# CANSniftAndShift.net
KiCad netlist of a schematic drawn in EAGLE
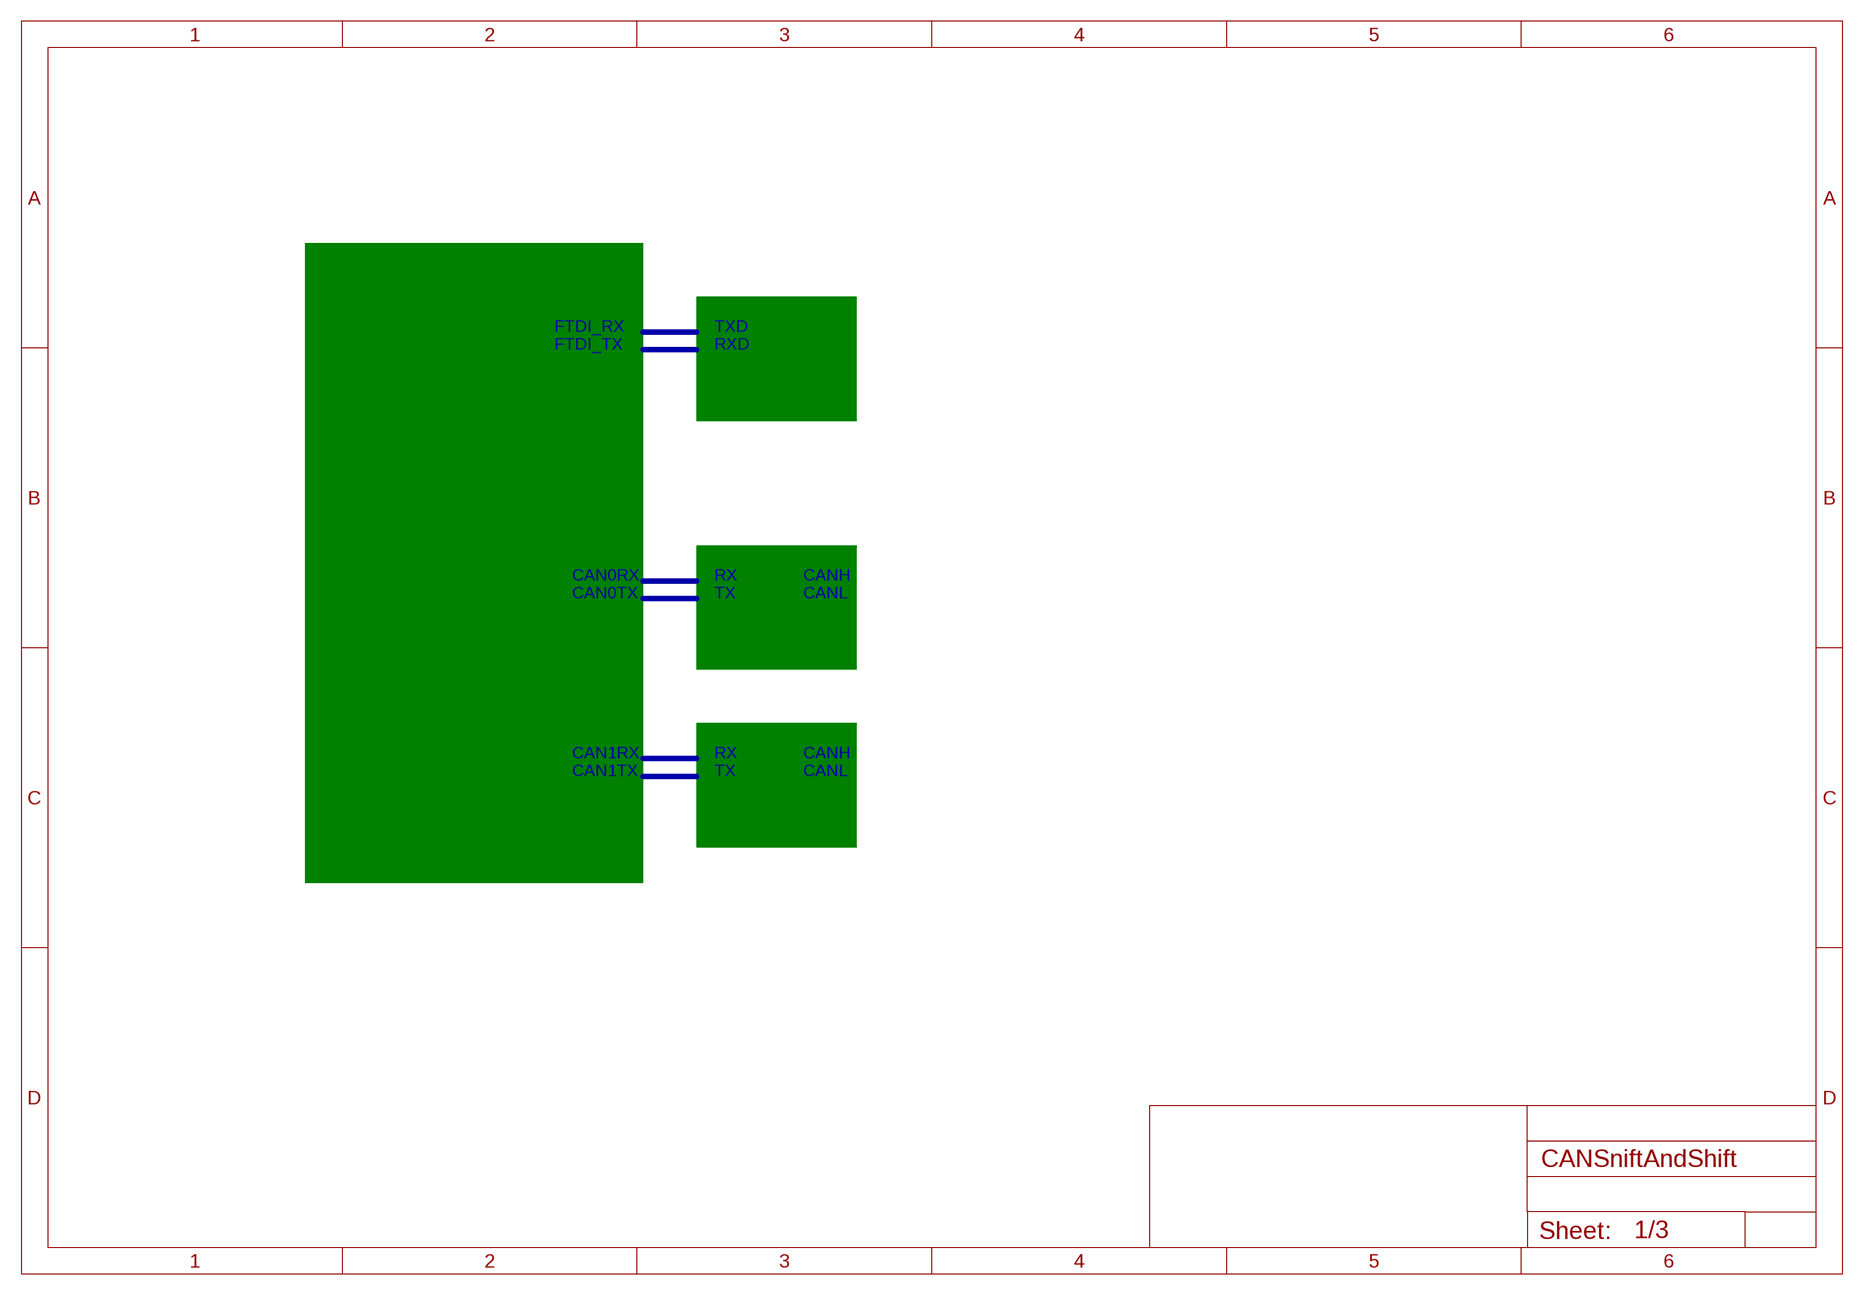
[diagram p0: schematic, sheet 1]
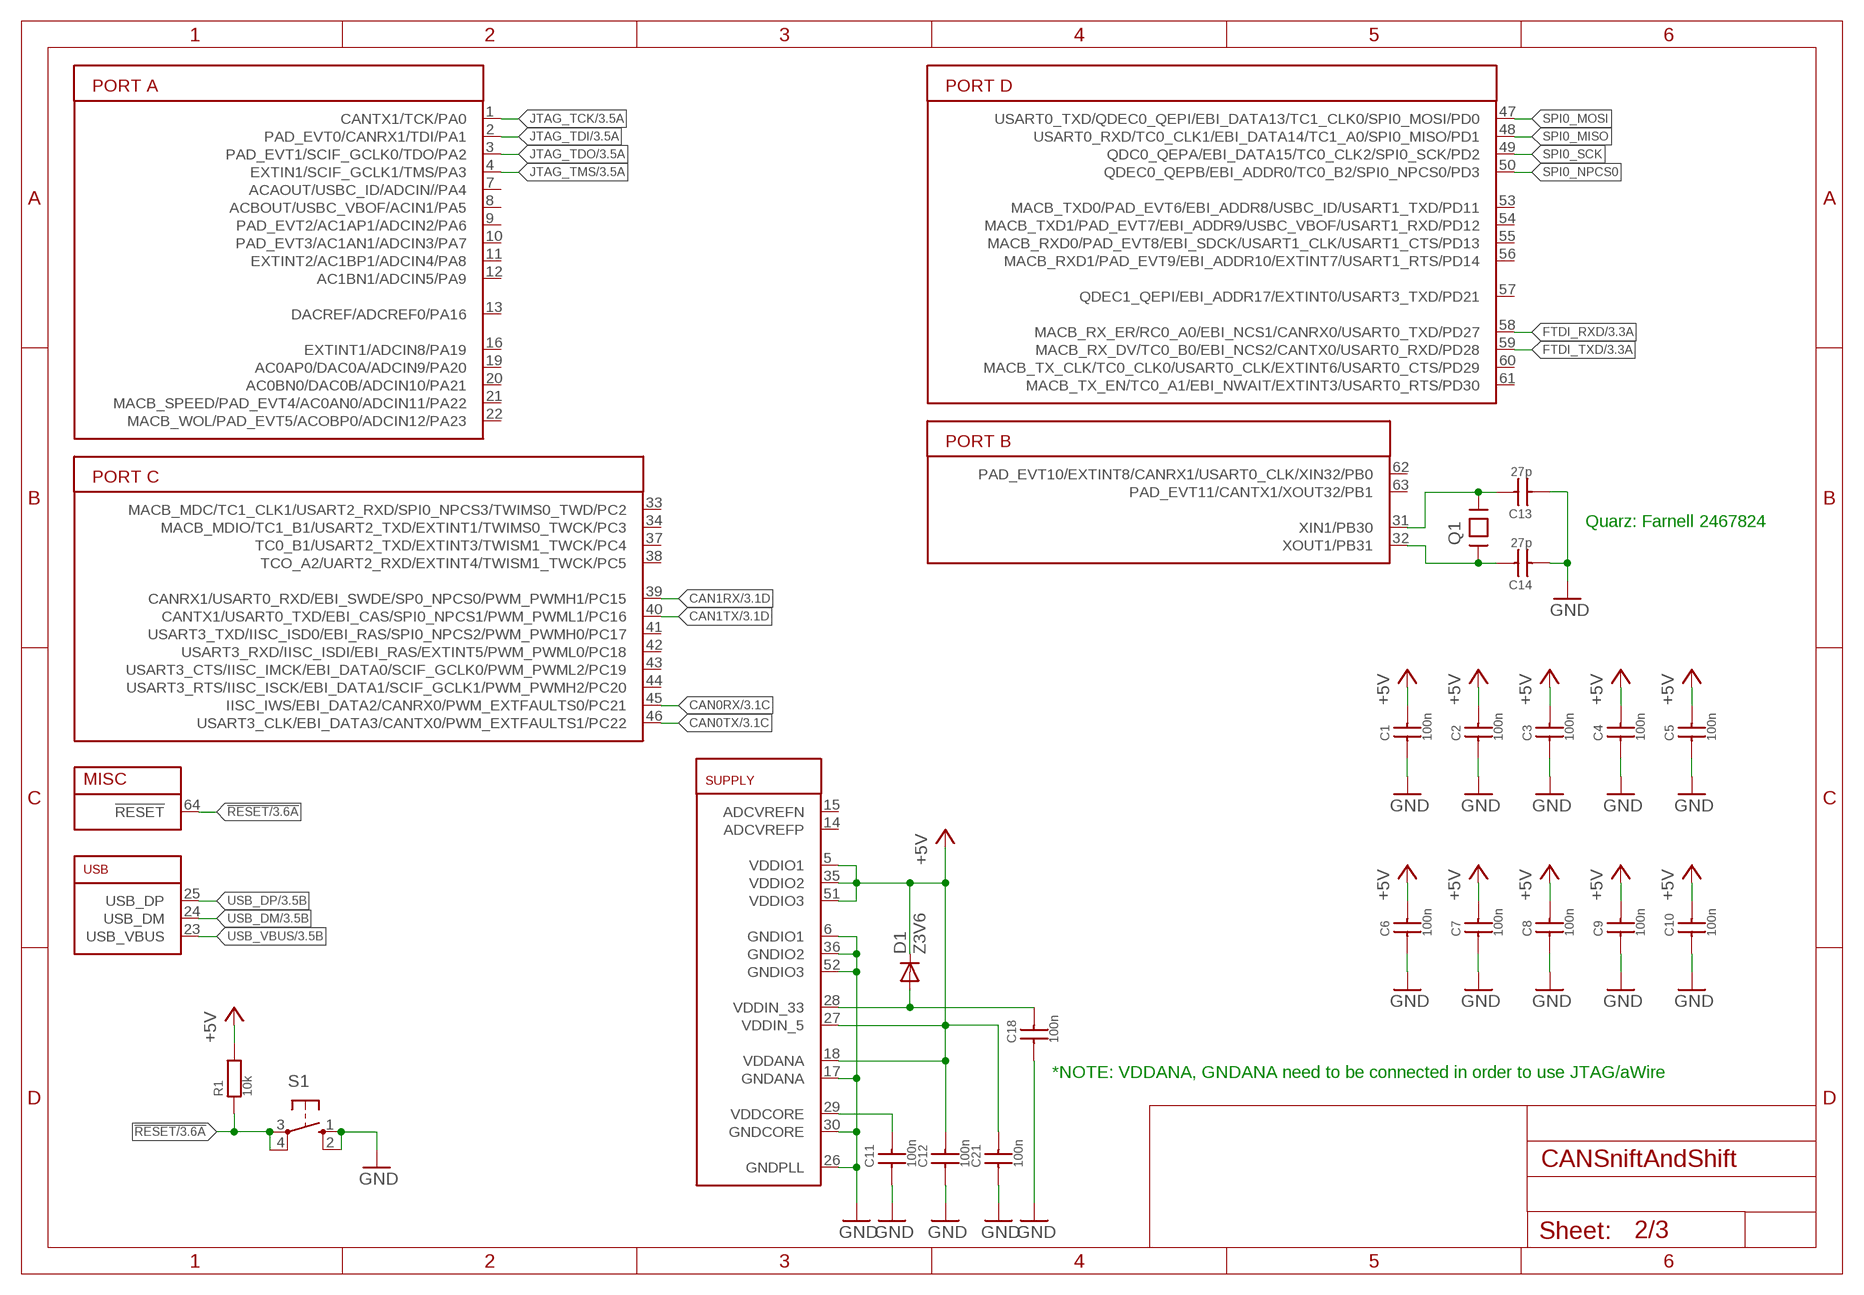
[diagram p1: schematic, sheet 2]
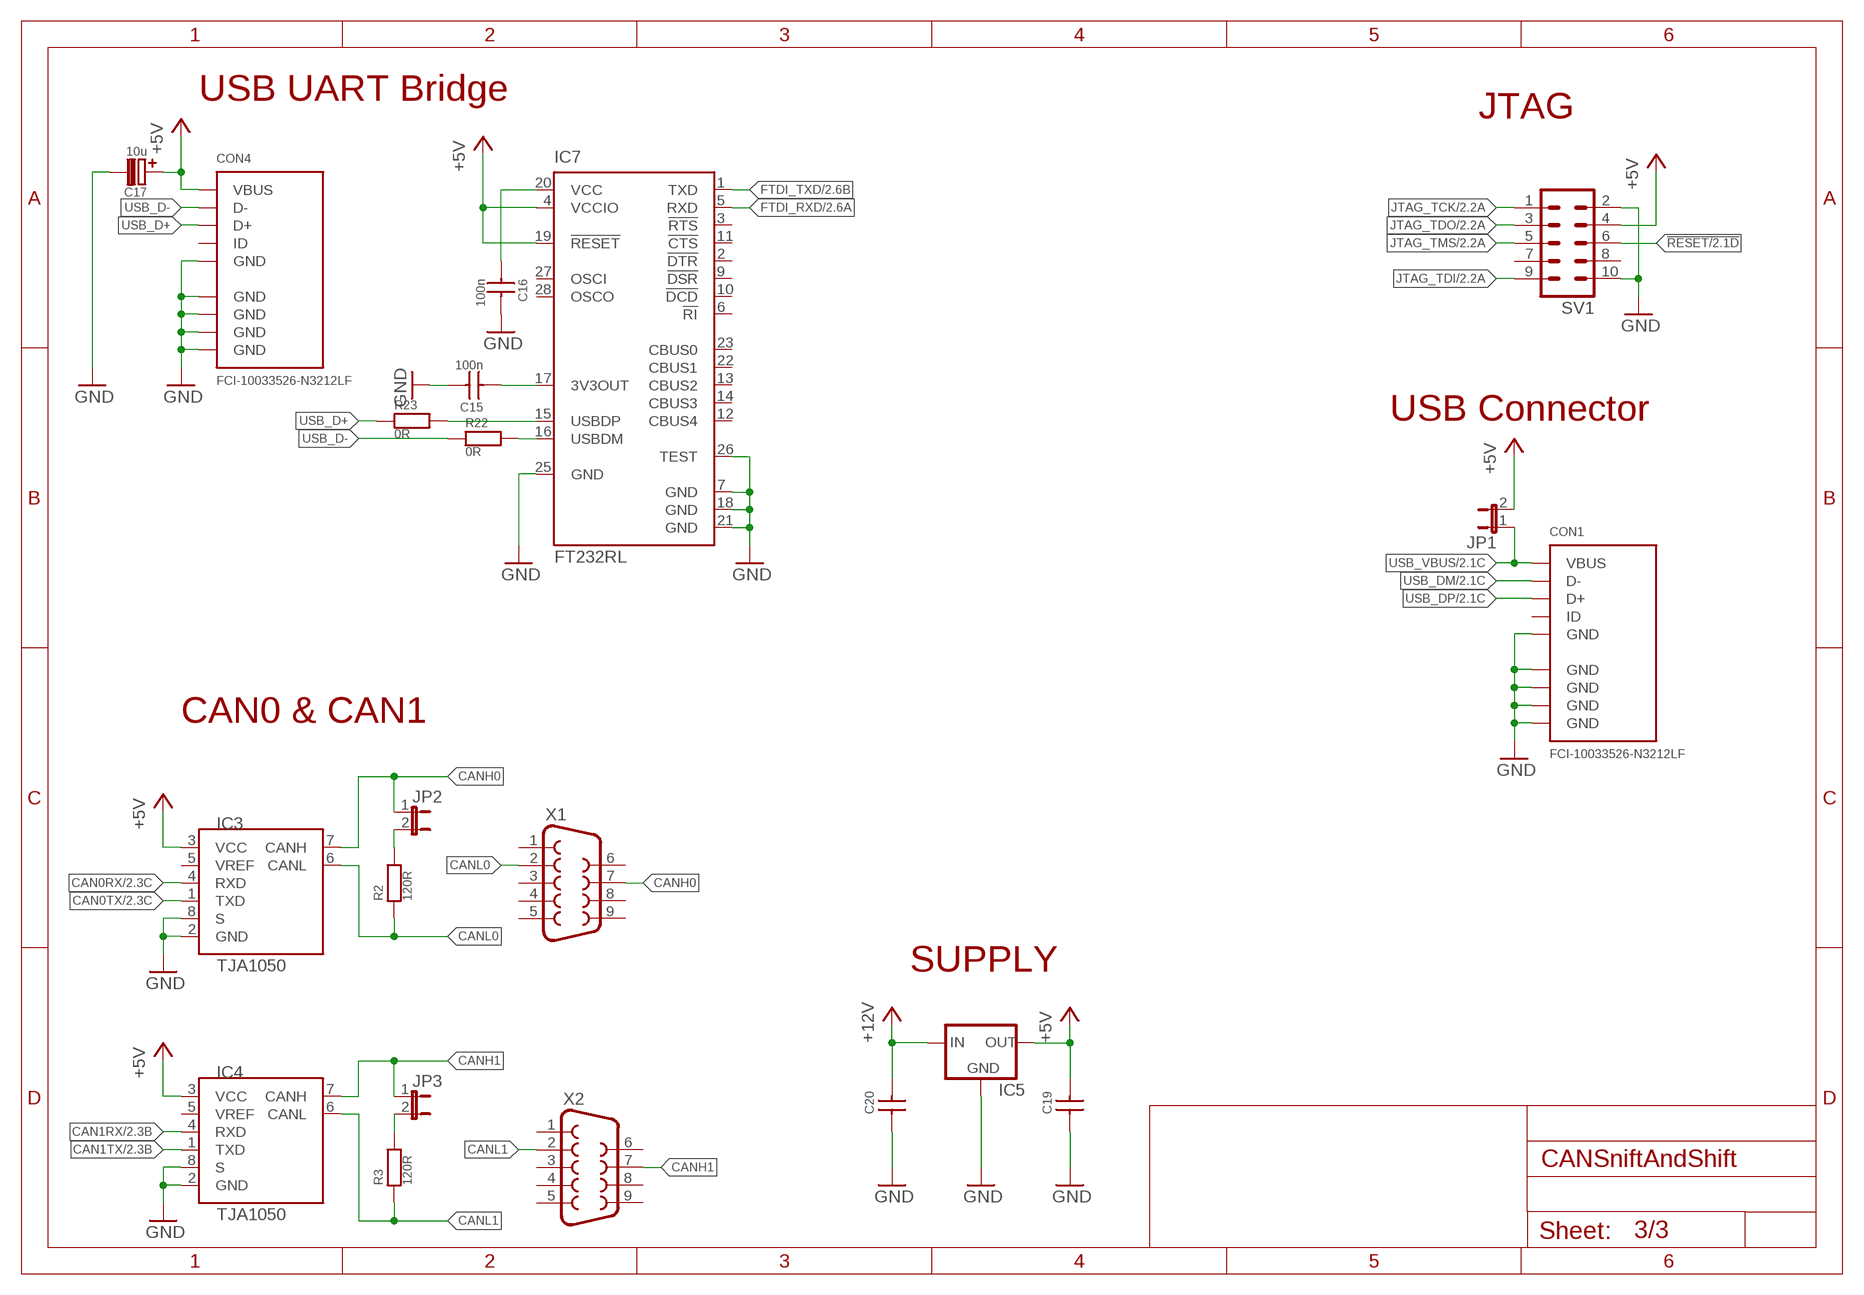
[diagram p2: schematic, sheet 3]

(export (version "E")
  (design (tool "Eeschema 10.0.6"))
  (components
    (comp (ref "C1")
      (value "100n")
      (footprint "eagle-import:C0603")
      (libsource (lib "eagle-import") (part "C_SMD0603"))
    )
    (comp (ref "C2")
      (value "100n")
      (footprint "eagle-import:C0603")
      (libsource (lib "eagle-import") (part "C_SMD0603"))
    )
    (comp (ref "C3")
      (value "100n")
      (footprint "eagle-import:C0603")
      (libsource (lib "eagle-import") (part "C_SMD0603"))
    )
    (comp (ref "C4")
      (value "100n")
      (footprint "eagle-import:C0603")
      (libsource (lib "eagle-import") (part "C_SMD0603"))
    )
    (comp (ref "C5")
      (value "100n")
      (footprint "eagle-import:C0603")
      (libsource (lib "eagle-import") (part "C_SMD0603"))
    )
    (comp (ref "C6")
      (value "100n")
      (footprint "eagle-import:C0603")
      (libsource (lib "eagle-import") (part "C_SMD0603"))
    )
    (comp (ref "C7")
      (value "100n")
      (footprint "eagle-import:C0603")
      (libsource (lib "eagle-import") (part "C_SMD0603"))
    )
    (comp (ref "C8")
      (value "100n")
      (footprint "eagle-import:C0603")
      (libsource (lib "eagle-import") (part "C_SMD0603"))
    )
    (comp (ref "C9")
      (value "100n")
      (footprint "eagle-import:C0603")
      (libsource (lib "eagle-import") (part "C_SMD0603"))
    )
    (comp (ref "C10")
      (value "100n")
      (footprint "eagle-import:C0603")
      (libsource (lib "eagle-import") (part "C_SMD0603"))
    )
    (comp (ref "C11")
      (value "100n")
      (footprint "eagle-import:C0603")
      (libsource (lib "eagle-import") (part "C_SMD0603"))
    )
    (comp (ref "C12")
      (value "100n")
      (footprint "eagle-import:C0603")
      (libsource (lib "eagle-import") (part "C_SMD0603"))
    )
    (comp (ref "C13")
      (value "27p")
      (footprint "eagle-import:C0603")
      (libsource (lib "eagle-import") (part "C_SMD0603"))
    )
    (comp (ref "C14")
      (value "27p")
      (footprint "eagle-import:C0603")
      (libsource (lib "eagle-import") (part "C_SMD0603"))
    )
    (comp (ref "C18")
      (value "100n")
      (footprint "eagle-import:C0603")
      (libsource (lib "eagle-import") (part "C_SMD0603"))
    )
    (comp (ref "C21")
      (value "100n")
      (footprint "eagle-import:C0603")
      (libsource (lib "eagle-import") (part "C_SMD0603"))
    )
    (comp (ref "D1")
      (value "Z3V6")
      (footprint "eagle-import:DO214A")
      (libsource (lib "eagle-import") (part "BZG03C15TR3"))
    )
    (comp (ref "IC1")
      (value "AT32UC3C264C0.5MM")
      (footprint "eagle-import:TQFP64-0.5MM")
      (libsource (lib "eagle-import") (part "AT32UC3C264C0.5MM"))
    )
    (comp (ref "Q1")
      (value "16MHz")
      (footprint "eagle-import:CRYSTAL-ABRACON-ABM7-SMD")
      (libsource (lib "eagle-import") (part "CRYSTAL-ABRACON-ABM7-SMD"))
    )
    (comp (ref "R1")
      (value "10k")
      (footprint "eagle-import:R0603")
      (libsource (lib "eagle-import") (part "R0603"))
    )
    (comp (ref "S1")
      (value "10-XX")
      (footprint "eagle-import:B3F-10XX")
      (fields (field (name "MPN") "B3F-1000"))
      (libsource (lib "eagle-import") (part "10-XX"))
    )
    (comp (ref "C15")
      (value "100n")
      (footprint "eagle-import:C0402")
      (libsource (lib "eagle-import") (part "C_SMD0402"))
    )
    (comp (ref "C16")
      (value "100n")
      (footprint "eagle-import:C0402")
      (libsource (lib "eagle-import") (part "C_SMD0402"))
    )
    (comp (ref "C17")
      (value "10u")
      (footprint "eagle-import:C_POL_4X4MM")
      (libsource (lib "eagle-import") (part "C_POL4X4MM"))
    )
    (comp (ref "C19")
      (value "C_SMD0603")
      (footprint "eagle-import:C0603")
      (libsource (lib "eagle-import") (part "C_SMD0603"))
    )
    (comp (ref "C20")
      (value "C_SMD0603")
      (footprint "eagle-import:C0603")
      (libsource (lib "eagle-import") (part "C_SMD0603"))
    )
    (comp (ref "CON1")
      (value "FCI-10033526-N3212LF")
      (footprint "eagle-import:FCI-10033526-N3212LF")
      (libsource (lib "eagle-import") (part "FCI-10033526-N3212LF"))
    )
    (comp (ref "CON4")
      (value "FCI-10033526-N3212LF")
      (footprint "eagle-import:FCI-10033526-N3212LF")
      (libsource (lib "eagle-import") (part "FCI-10033526-N3212LF"))
    )
    (comp (ref "IC3")
      (value "TJA1050")
      (footprint "eagle-import:SO8")
      (libsource (lib "eagle-import") (part "TJA1050"))
    )
    (comp (ref "IC4")
      (value "TJA1050")
      (footprint "eagle-import:SO8")
      (libsource (lib "eagle-import") (part "TJA1050"))
    )
    (comp (ref "IC5")
      (value "78XXL")
      (footprint "eagle-import:78XXL")
      (libsource (lib "eagle-import") (part "78XXL"))
    )
    (comp (ref "IC7")
      (value "FT232RL")
      (footprint "eagle-import:SSOP28")
      (libsource (lib "eagle-import") (part "FT232RL"))
    )
    (comp (ref "JP1")
      (value "JUMPER2")
      (footprint "eagle-import:JUMPER2_THROUGHHOLE")
      (libsource (lib "eagle-import") (part "JUMPER2"))
    )
    (comp (ref "JP2")
      (value "JUMPER2")
      (footprint "eagle-import:JUMPER2_THROUGHHOLE")
      (libsource (lib "eagle-import") (part "JUMPER2"))
    )
    (comp (ref "JP3")
      (value "JUMPER2")
      (footprint "eagle-import:JUMPER2_THROUGHHOLE")
      (libsource (lib "eagle-import") (part "JUMPER2"))
    )
    (comp (ref "R2")
      (value "120R")
      (footprint "eagle-import:R0603")
      (libsource (lib "eagle-import") (part "R0603"))
    )
    (comp (ref "R3")
      (value "120R")
      (footprint "eagle-import:R0603")
      (libsource (lib "eagle-import") (part "R0603"))
    )
    (comp (ref "R22")
      (value "0R")
      (footprint "eagle-import:R0402")
      (libsource (lib "eagle-import") (part "R0402"))
    )
    (comp (ref "R23")
      (value "0R")
      (footprint "eagle-import:R0402")
      (libsource (lib "eagle-import") (part "R0402"))
    )
    (comp (ref "SV1")
      (value "ML10")
      (footprint "eagle-import:ML10")
      (libsource (lib "eagle-import") (part "ML10"))
    )
    (comp (ref "X1")
      (value "F09HP")
      (footprint "eagle-import:F09HP")
      (libsource (lib "eagle-import") (part "F09HP"))
    )
    (comp (ref "X2")
      (value "F09HP")
      (footprint "eagle-import:F09HP")
      (libsource (lib "eagle-import") (part "F09HP"))
    )
  )
  (nets
    (net (code "1") (name "+5V") (class "Default")
      (node (ref "C1") (pin "2") (pinfunction "P$2_2") (pintype "passive"))
      (node (ref "C10") (pin "2") (pinfunction "P$2_2") (pintype "passive"))
      (node (ref "C12") (pin "2") (pinfunction "P$2_2") (pintype "passive"))
      (node (ref "C17") (pin "+") (pinfunction "+_+") (pintype "passive"))
      (node (ref "C19") (pin "2") (pinfunction "P$2_2") (pintype "passive"))
      (node (ref "C2") (pin "2") (pinfunction "P$2_2") (pintype "passive"))
      (node (ref "C21") (pin "2") (pinfunction "P$2_2") (pintype "passive"))
      (node (ref "C3") (pin "2") (pinfunction "P$2_2") (pintype "passive"))
      (node (ref "C4") (pin "2") (pinfunction "P$2_2") (pintype "passive"))
      (node (ref "C5") (pin "2") (pinfunction "P$2_2") (pintype "passive"))
      (node (ref "C6") (pin "2") (pinfunction "P$2_2") (pintype "passive"))
      (node (ref "C7") (pin "2") (pinfunction "P$2_2") (pintype "passive"))
      (node (ref "C8") (pin "2") (pinfunction "P$2_2") (pintype "passive"))
      (node (ref "C9") (pin "2") (pinfunction "P$2_2") (pintype "passive"))
      (node (ref "CON4") (pin "1") (pinfunction "VBUS_1") (pintype "bidirectional"))
      (node (ref "D1") (pin "C") (pinfunction "C_C") (pintype "passive"))
      (node (ref "IC1") (pin "18") (pinfunction "VDDANA_18") (pintype "bidirectional"))
      (node (ref "IC1") (pin "27") (pinfunction "VDDIN_5_27") (pintype "bidirectional"))
      (node (ref "IC1") (pin "35") (pinfunction "VDDIO2_35") (pintype "bidirectional"))
      (node (ref "IC1") (pin "5") (pinfunction "VDDIO1_5") (pintype "bidirectional"))
      (node (ref "IC1") (pin "51") (pinfunction "VDDIO3_51") (pintype "bidirectional"))
      (node (ref "IC3") (pin "3") (pinfunction "VCC_3") (pintype "bidirectional"))
      (node (ref "IC4") (pin "3") (pinfunction "VCC_3") (pintype "bidirectional"))
      (node (ref "IC5") (pin "OUT") (pinfunction "OUT_OUT") (pintype "passive"))
      (node (ref "IC7") (pin "19") (pinfunction "~{RESET}_19") (pintype "input"))
      (node (ref "IC7") (pin "4") (pinfunction "VCCIO_4") (pintype "power_in"))
      (node (ref "JP1") (pin "2") (pinfunction "2_2") (pintype "passive"))
      (node (ref "R1") (pin "2") (pinfunction "P$2_2") (pintype "passive"))
      (node (ref "SV1") (pin "4") (pinfunction "4_4") (pintype "passive"))
    )
    (net (code "2") (name "+12V") (class "Default")
      (node (ref "C20") (pin "2") (pinfunction "P$2_2") (pintype "passive"))
      (node (ref "IC5") (pin "IN") (pinfunction "IN_IN") (pintype "input"))
    )
    (net (code "3") (name "CAN0RX") (class "Default")
      (node (ref "IC1") (pin "45") (pinfunction "IISC_IWS/EBI_DATA2/CANRX0/PWM_EXTFAULTS0/PC21_45") (pintype "bidirectional"))
      (node (ref "IC3") (pin "4") (pinfunction "RXD_4") (pintype "bidirectional"))
    )
    (net (code "4") (name "CAN0TX") (class "Default")
      (node (ref "IC1") (pin "46") (pinfunction "USART3_CLK/EBI_DATA3/CANTX0/PWM_EXTFAULTS1/PC22_46") (pintype "bidirectional"))
      (node (ref "IC3") (pin "1") (pinfunction "TXD_1") (pintype "bidirectional"))
    )
    (net (code "5") (name "CAN1RX") (class "Default")
      (node (ref "IC1") (pin "39") (pinfunction "CANRX1/USART0_RXD/EBI_SWDE/SP0_NPCS0/PWM_PWMH1/PC15_39") (pintype "bidirectional"))
      (node (ref "IC4") (pin "4") (pinfunction "RXD_4") (pintype "bidirectional"))
    )
    (net (code "6") (name "CAN1TX") (class "Default")
      (node (ref "IC1") (pin "40") (pinfunction "CANTX1/USART0_TXD/EBI_CAS/SPI0_NPCS1/PWM_PWML1/PC16_40") (pintype "bidirectional"))
      (node (ref "IC4") (pin "1") (pinfunction "TXD_1") (pintype "bidirectional"))
    )
    (net (code "7") (name "CANH0") (class "Default")
      (node (ref "IC3") (pin "7") (pinfunction "CANH_7") (pintype "bidirectional"))
      (node (ref "JP2") (pin "1") (pinfunction "1_1") (pintype "passive"))
      (node (ref "X1") (pin "7") (pinfunction "7_7") (pintype "passive"))
    )
    (net (code "8") (name "CANH1") (class "Default")
      (node (ref "IC4") (pin "7") (pinfunction "CANH_7") (pintype "bidirectional"))
      (node (ref "JP3") (pin "1") (pinfunction "1_1") (pintype "passive"))
      (node (ref "X2") (pin "7") (pinfunction "7_7") (pintype "passive"))
    )
    (net (code "9") (name "CANL0") (class "Default")
      (node (ref "IC3") (pin "6") (pinfunction "CANL_6") (pintype "bidirectional"))
      (node (ref "R2") (pin "1") (pinfunction "P$1_1") (pintype "passive"))
      (node (ref "X1") (pin "2") (pinfunction "2_2") (pintype "passive"))
    )
    (net (code "10") (name "CANL1") (class "Default")
      (node (ref "IC4") (pin "6") (pinfunction "CANL_6") (pintype "bidirectional"))
      (node (ref "R3") (pin "1") (pinfunction "P$1_1") (pintype "passive"))
      (node (ref "X2") (pin "2") (pinfunction "2_2") (pintype "passive"))
    )
    (net (code "11") (name "FTDI_RXD") (class "Default")
      (node (ref "IC1") (pin "58") (pinfunction "MACB_RX_ER/RC0_A0/EBI_NCS1/CANRX0/USART0_TXD/PD27_58") (pintype "bidirectional"))
      (node (ref "IC7") (pin "5") (pinfunction "RXD_5") (pintype "input"))
    )
    (net (code "12") (name "FTDI_TXD") (class "Default")
      (node (ref "IC1") (pin "59") (pinfunction "MACB_RX_DV/TC0_B0/EBI_NCS2/CANTX0/USART0_RXD/PD28_59") (pintype "bidirectional"))
      (node (ref "IC7") (pin "1") (pinfunction "TXD_1") (pintype "output"))
    )
    (net (code "13") (name "GND") (class "Default")
      (node (ref "C1") (pin "1") (pinfunction "P$1_1") (pintype "passive"))
      (node (ref "C10") (pin "1") (pinfunction "P$1_1") (pintype "passive"))
      (node (ref "C11") (pin "1") (pinfunction "P$1_1") (pintype "passive"))
      (node (ref "C12") (pin "1") (pinfunction "P$1_1") (pintype "passive"))
      (node (ref "C13") (pin "1") (pinfunction "P$1_1") (pintype "passive"))
      (node (ref "C14") (pin "1") (pinfunction "P$1_1") (pintype "passive"))
      (node (ref "C15") (pin "2") (pinfunction "P$2_2") (pintype "passive"))
      (node (ref "C16") (pin "2") (pinfunction "P$2_2") (pintype "passive"))
      (node (ref "C17") (pin "-") (pinfunction "-_-") (pintype "passive"))
      (node (ref "C18") (pin "1") (pinfunction "P$1_1") (pintype "passive"))
      (node (ref "C19") (pin "1") (pinfunction "P$1_1") (pintype "passive"))
      (node (ref "C2") (pin "1") (pinfunction "P$1_1") (pintype "passive"))
      (node (ref "C20") (pin "1") (pinfunction "P$1_1") (pintype "passive"))
      (node (ref "C21") (pin "1") (pinfunction "P$1_1") (pintype "passive"))
      (node (ref "C3") (pin "1") (pinfunction "P$1_1") (pintype "passive"))
      (node (ref "C4") (pin "1") (pinfunction "P$1_1") (pintype "passive"))
      (node (ref "C5") (pin "1") (pinfunction "P$1_1") (pintype "passive"))
      (node (ref "C6") (pin "1") (pinfunction "P$1_1") (pintype "passive"))
      (node (ref "C7") (pin "1") (pinfunction "P$1_1") (pintype "passive"))
      (node (ref "C8") (pin "1") (pinfunction "P$1_1") (pintype "passive"))
      (node (ref "C9") (pin "1") (pinfunction "P$1_1") (pintype "passive"))
      (node (ref "CON1") (pin "5") (pinfunction "GND_5") (pintype "bidirectional"))
      (node (ref "CON1") (pin "GND@1") (pinfunction "GND_GND@1") (pintype "power_in"))
      (node (ref "CON1") (pin "GND@2") (pinfunction "GND_GND@2") (pintype "power_in"))
      (node (ref "CON1") (pin "GND@3") (pinfunction "GND_GND@3") (pintype "power_in"))
      (node (ref "CON1") (pin "GND@4") (pinfunction "GND_GND@4") (pintype "power_in"))
      (node (ref "CON4") (pin "5") (pinfunction "GND_5") (pintype "bidirectional"))
      (node (ref "CON4") (pin "GND@1") (pinfunction "GND_GND@1") (pintype "power_in"))
      (node (ref "CON4") (pin "GND@2") (pinfunction "GND_GND@2") (pintype "power_in"))
      (node (ref "CON4") (pin "GND@3") (pinfunction "GND_GND@3") (pintype "power_in"))
      (node (ref "CON4") (pin "GND@4") (pinfunction "GND_GND@4") (pintype "power_in"))
      (node (ref "IC1") (pin "17") (pinfunction "GNDANA_17") (pintype "bidirectional"))
      (node (ref "IC1") (pin "26") (pinfunction "GNDPLL_26") (pintype "bidirectional"))
      (node (ref "IC1") (pin "30") (pinfunction "GNDCORE_30") (pintype "bidirectional"))
      (node (ref "IC1") (pin "36") (pinfunction "GNDIO2_36") (pintype "bidirectional"))
      (node (ref "IC1") (pin "52") (pinfunction "GNDIO3_52") (pintype "bidirectional"))
      (node (ref "IC1") (pin "6") (pinfunction "GNDIO1_6") (pintype "bidirectional"))
      (node (ref "IC3") (pin "2") (pinfunction "GND_2") (pintype "bidirectional"))
      (node (ref "IC3") (pin "8") (pinfunction "S_8") (pintype "bidirectional"))
      (node (ref "IC4") (pin "2") (pinfunction "GND_2") (pintype "bidirectional"))
      (node (ref "IC4") (pin "8") (pinfunction "S_8") (pintype "bidirectional"))
      (node (ref "IC5") (pin "GND") (pinfunction "GND_GND") (pintype "input"))
      (node (ref "IC7") (pin "18") (pinfunction "GND_18") (pintype "power_in"))
      (node (ref "IC7") (pin "21") (pinfunction "GND_21") (pintype "power_in"))
      (node (ref "IC7") (pin "25") (pinfunction "GND_25") (pintype "power_in"))
      (node (ref "IC7") (pin "26") (pinfunction "TEST_26") (pintype "input"))
      (node (ref "IC7") (pin "7") (pinfunction "GND_7") (pintype "power_in"))
      (node (ref "S1") (pin "1") (pinfunction "S_1") (pintype "passive"))
      (node (ref "S1") (pin "2") (pinfunction "S1_2") (pintype "passive"))
      (node (ref "SV1") (pin "10") (pinfunction "10_10") (pintype "passive"))
      (node (ref "SV1") (pin "2") (pinfunction "2_2") (pintype "passive"))
    )
    (net (code "14") (name "JTAG_TCK") (class "Default")
      (node (ref "IC1") (pin "1") (pinfunction "CANTX1/TCK/PA0_1") (pintype "bidirectional"))
      (node (ref "SV1") (pin "1") (pinfunction "1_1") (pintype "passive"))
    )
    (net (code "15") (name "JTAG_TDI") (class "Default")
      (node (ref "IC1") (pin "2") (pinfunction "PAD_EVT0/CANRX1/TDI/PA1_2") (pintype "bidirectional"))
      (node (ref "SV1") (pin "9") (pinfunction "9_9") (pintype "passive"))
    )
    (net (code "16") (name "JTAG_TDO") (class "Default")
      (node (ref "IC1") (pin "3") (pinfunction "PAD_EVT1/SCIF_GCLK0/TDO/PA2_3") (pintype "bidirectional"))
      (node (ref "SV1") (pin "3") (pinfunction "3_3") (pintype "passive"))
    )
    (net (code "17") (name "JTAG_TMS") (class "Default")
      (node (ref "IC1") (pin "4") (pinfunction "EXTIN1/SCIF_GCLK1/TMS/PA3_4") (pintype "bidirectional"))
      (node (ref "SV1") (pin "5") (pinfunction "5_5") (pintype "passive"))
    )
    (net (code "18") (name "Net-(C11-P$2)") (class "Default")
      (node (ref "C11") (pin "2") (pinfunction "P$2_2") (pintype "passive"))
      (node (ref "IC1") (pin "29") (pinfunction "VDDCORE_29") (pintype "bidirectional"))
    )
    (net (code "19") (name "Net-(C13-P$2)") (class "Default")
      (node (ref "C13") (pin "2") (pinfunction "P$2_2") (pintype "passive"))
      (node (ref "IC1") (pin "31") (pinfunction "XIN1/PB30_31") (pintype "bidirectional"))
      (node (ref "Q1") (pin "P$2") (pinfunction "P$2_P$2") (pintype "bidirectional"))
    )
    (net (code "20") (name "Net-(C14-P$2)") (class "Default")
      (node (ref "C14") (pin "2") (pinfunction "P$2_2") (pintype "passive"))
      (node (ref "IC1") (pin "32") (pinfunction "XOUT1/PB31_32") (pintype "bidirectional"))
      (node (ref "Q1") (pin "P$1") (pinfunction "P$1_P$1") (pintype "bidirectional"))
    )
    (net (code "21") (name "Net-(C15-P$1)") (class "Default")
      (node (ref "C15") (pin "1") (pinfunction "P$1_1") (pintype "passive"))
      (node (ref "IC7") (pin "17") (pinfunction "3V3OUT_17") (pintype "output"))
    )
    (net (code "22") (name "Net-(C16-P$1)") (class "Default")
      (node (ref "C16") (pin "1") (pinfunction "P$1_1") (pintype "passive"))
      (node (ref "IC7") (pin "20") (pinfunction "VCC_20") (pintype "power_in"))
    )
    (net (code "23") (name "Net-(C18-P$2)") (class "Default")
      (node (ref "C18") (pin "2") (pinfunction "P$2_2") (pintype "passive"))
      (node (ref "D1") (pin "A") (pinfunction "A_A") (pintype "passive"))
      (node (ref "IC1") (pin "28") (pinfunction "VDDIN_33_28") (pintype "bidirectional"))
    )
    (net (code "24") (name "Net-(IC7-USBDM)") (class "Default")
      (node (ref "IC7") (pin "16") (pinfunction "USBDM_16") (pintype "bidirectional"))
      (node (ref "R22") (pin "2") (pinfunction "P$2_2") (pintype "passive"))
    )
    (net (code "25") (name "Net-(IC7-USBDP)") (class "Default")
      (node (ref "IC7") (pin "15") (pinfunction "USBDP_15") (pintype "bidirectional"))
      (node (ref "R23") (pin "2") (pinfunction "P$2_2") (pintype "passive"))
    )
    (net (code "26") (name "Net-(R2-P$2)") (class "Default")
      (node (ref "JP2") (pin "2") (pinfunction "2_2") (pintype "passive"))
      (node (ref "R2") (pin "2") (pinfunction "P$2_2") (pintype "passive"))
    )
    (net (code "27") (name "Net-(R3-P$2)") (class "Default")
      (node (ref "JP3") (pin "2") (pinfunction "2_2") (pintype "passive"))
      (node (ref "R3") (pin "2") (pinfunction "P$2_2") (pintype "passive"))
    )
    (net (code "28") (name "SPI0_MISO") (class "Default")
      (node (ref "IC1") (pin "48") (pinfunction "USART0_RXD/TC0_CLK1/EBI_DATA14/TC1_A0/SPI0_MISO/PD1_48") (pintype "bidirectional"))
    )
    (net (code "29") (name "SPI0_MOSI") (class "Default")
      (node (ref "IC1") (pin "47") (pinfunction "USART0_TXD/QDEC0_QEPI/EBI_DATA13/TC1_CLK0/SPI0_MOSI/PD0_47") (pintype "bidirectional"))
    )
    (net (code "30") (name "SPI0_NPCS0") (class "Default")
      (node (ref "IC1") (pin "50") (pinfunction "QDEC0_QEPB/EBI_ADDR0/TC0_B2/SPI0_NPCS0/PD3_50") (pintype "bidirectional"))
    )
    (net (code "31") (name "SPI0_SCK") (class "Default")
      (node (ref "IC1") (pin "49") (pinfunction "QDC0_QEPA/EBI_DATA15/TC0_CLK2/SPI0_SCK/PD2_49") (pintype "bidirectional"))
    )
    (net (code "32") (name "USB_D+") (class "Default")
      (node (ref "CON4") (pin "3") (pinfunction "D+_3") (pintype "bidirectional"))
      (node (ref "R23") (pin "1") (pinfunction "P$1_1") (pintype "passive"))
    )
    (net (code "33") (name "USB_D-") (class "Default")
      (node (ref "CON4") (pin "2") (pinfunction "D-_2") (pintype "bidirectional"))
      (node (ref "R22") (pin "1") (pinfunction "P$1_1") (pintype "passive"))
    )
    (net (code "34") (name "USB_DM") (class "Default")
      (node (ref "CON1") (pin "2") (pinfunction "D-_2") (pintype "bidirectional"))
      (node (ref "IC1") (pin "24") (pinfunction "USB_DM_24") (pintype "bidirectional"))
    )
    (net (code "35") (name "USB_DP") (class "Default")
      (node (ref "CON1") (pin "3") (pinfunction "D+_3") (pintype "bidirectional"))
      (node (ref "IC1") (pin "25") (pinfunction "USB_DP_25") (pintype "bidirectional"))
    )
    (net (code "36") (name "USB_VBUS") (class "Default")
      (node (ref "CON1") (pin "1") (pinfunction "VBUS_1") (pintype "bidirectional"))
      (node (ref "IC1") (pin "23") (pinfunction "USB_VBUS_23") (pintype "bidirectional"))
      (node (ref "JP1") (pin "1") (pinfunction "1_1") (pintype "passive"))
    )
    (net (code "37") (name "unconnected-(CON1-ID-Pad4)") (class "Default")
      (node (ref "CON1") (pin "4") (pinfunction "ID_4") (pintype "bidirectional"))
    )
    (net (code "38") (name "unconnected-(CON4-ID-Pad4)") (class "Default")
      (node (ref "CON4") (pin "4") (pinfunction "ID_4") (pintype "bidirectional"))
    )
    (net (code "39") (name "unconnected-(IC1B-AC0AP0{slash}DAC0A{slash}ADCIN9{slash}PA20-Pad19)") (class "Default")
      (node (ref "IC1") (pin "19") (pinfunction "AC0AP0/DAC0A/ADCIN9/PA20_19") (pintype "bidirectional"))
    )
    (net (code "40") (name "unconnected-(IC1B-AC0BN0{slash}DAC0B{slash}ADCIN10{slash}PA21-Pad20)") (class "Default")
      (node (ref "IC1") (pin "20") (pinfunction "AC0BN0/DAC0B/ADCIN10/PA21_20") (pintype "bidirectional"))
    )
    (net (code "41") (name "unconnected-(IC1B-AC1BN1{slash}ADCIN5{slash}PA9-Pad12)") (class "Default")
      (node (ref "IC1") (pin "12") (pinfunction "AC1BN1/ADCIN5/PA9_12") (pintype "bidirectional"))
    )
    (net (code "42") (name "unconnected-(IC1B-ACAOUT{slash}USBC_ID{slash}ADCIN{slash}{slash}PA4-Pad7)") (class "Default")
      (node (ref "IC1") (pin "7") (pinfunction "ACAOUT/USBC_ID/ADCIN//PA4_7") (pintype "bidirectional"))
    )
    (net (code "43") (name "unconnected-(IC1B-ACBOUT{slash}USBC_VBOF{slash}ACIN1{slash}PA5-Pad8)") (class "Default")
      (node (ref "IC1") (pin "8") (pinfunction "ACBOUT/USBC_VBOF/ACIN1/PA5_8") (pintype "bidirectional"))
    )
    (net (code "44") (name "unconnected-(IC1B-DACREF{slash}ADCREF0{slash}PA16-Pad13)") (class "Default")
      (node (ref "IC1") (pin "13") (pinfunction "DACREF/ADCREF0/PA16_13") (pintype "bidirectional"))
    )
    (net (code "45") (name "unconnected-(IC1B-EXTINT1{slash}ADCIN8{slash}PA19-Pad16)") (class "Default")
      (node (ref "IC1") (pin "16") (pinfunction "EXTINT1/ADCIN8/PA19_16") (pintype "bidirectional"))
    )
    (net (code "46") (name "unconnected-(IC1B-EXTINT2{slash}AC1BP1{slash}ADCIN4{slash}PA8-Pad11)") (class "Default")
      (node (ref "IC1") (pin "11") (pinfunction "EXTINT2/AC1BP1/ADCIN4/PA8_11") (pintype "bidirectional"))
    )
    (net (code "47") (name "unconnected-(IC1B-MACB_SPEED{slash}PAD_EVT4{slash}AC0AN0{slash}ADCIN11{slash}PA22-Pad21)") (class "Default")
      (node (ref "IC1") (pin "21") (pinfunction "MACB_SPEED/PAD_EVT4/AC0AN0/ADCIN11/PA22_21") (pintype "bidirectional"))
    )
    (net (code "48") (name "unconnected-(IC1B-MACB_WOL{slash}PAD_EVT5{slash}ACOBP0{slash}ADCIN12{slash}PA23-Pad22)") (class "Default")
      (node (ref "IC1") (pin "22") (pinfunction "MACB_WOL/PAD_EVT5/ACOBP0/ADCIN12/PA23_22") (pintype "bidirectional"))
    )
    (net (code "49") (name "unconnected-(IC1B-PAD_EVT2{slash}AC1AP1{slash}ADCIN2{slash}PA6-Pad9)") (class "Default")
      (node (ref "IC1") (pin "9") (pinfunction "PAD_EVT2/AC1AP1/ADCIN2/PA6_9") (pintype "bidirectional"))
    )
    (net (code "50") (name "unconnected-(IC1B-PAD_EVT3{slash}AC1AN1{slash}ADCIN3{slash}PA7-Pad10)") (class "Default")
      (node (ref "IC1") (pin "10") (pinfunction "PAD_EVT3/AC1AN1/ADCIN3/PA7_10") (pintype "bidirectional"))
    )
    (net (code "51") (name "unconnected-(IC1C-PAD_EVT10{slash}EXTINT8{slash}CANRX1{slash}USART0_CLK{slash}XIN32{slash}PB0-Pad62)") (class "Default")
      (node (ref "IC1") (pin "62") (pinfunction "PAD_EVT10/EXTINT8/CANRX1/USART0_CLK/XIN32/PB0_62") (pintype "bidirectional"))
    )
    (net (code "52") (name "unconnected-(IC1C-PAD_EVT11{slash}CANTX1{slash}XOUT32{slash}PB1-Pad63)") (class "Default")
      (node (ref "IC1") (pin "63") (pinfunction "PAD_EVT11/CANTX1/XOUT32/PB1_63") (pintype "bidirectional"))
    )
    (net (code "53") (name "unconnected-(IC1D-MACB_MDC{slash}TC1_CLK1{slash}USART2_RXD{slash}SPI0_NPCS3{slash}TWIMS0_TWD{slash}PC2-Pad33)") (class "Default")
      (node (ref "IC1") (pin "33") (pinfunction "MACB_MDC/TC1_CLK1/USART2_RXD/SPI0_NPCS3/TWIMS0_TWD/PC2_33") (pintype "bidirectional"))
    )
    (net (code "54") (name "unconnected-(IC1D-MACB_MDIO{slash}TC1_B1{slash}USART2_TXD{slash}EXTINT1{slash}TWIMS0_TWCK{slash}PC3-Pad34)") (class "Default")
      (node (ref "IC1") (pin "34") (pinfunction "MACB_MDIO/TC1_B1/USART2_TXD/EXTINT1/TWIMS0_TWCK/PC3_34") (pintype "bidirectional"))
    )
    (net (code "55") (name "unconnected-(IC1D-TC0_B1{slash}USART2_TXD{slash}EXTINT3{slash}TWISM1_TWCK{slash}PC4-Pad37)") (class "Default")
      (node (ref "IC1") (pin "37") (pinfunction "TC0_B1/USART2_TXD/EXTINT3/TWISM1_TWCK/PC4_37") (pintype "bidirectional"))
    )
    (net (code "56") (name "unconnected-(IC1D-TCO_A2{slash}UART2_RXD{slash}EXTINT4{slash}TWISM1_TWCK{slash}PC5-Pad38)") (class "Default")
      (node (ref "IC1") (pin "38") (pinfunction "TCO_A2/UART2_RXD/EXTINT4/TWISM1_TWCK/PC5_38") (pintype "bidirectional"))
    )
    (net (code "57") (name "unconnected-(IC1D-USART3_CTS{slash}IISC_IMCK{slash}EBI_DATA0{slash}SCIF_GCLK0{slash}PWM_PWML2{slash}PC19-Pad43)") (class "Default")
      (node (ref "IC1") (pin "43") (pinfunction "USART3_CTS/IISC_IMCK/EBI_DATA0/SCIF_GCLK0/PWM_PWML2/PC19_43") (pintype "bidirectional"))
    )
    (net (code "58") (name "unconnected-(IC1D-USART3_RTS{slash}IISC_ISCK{slash}EBI_DATA1{slash}SCIF_GCLK1{slash}PWM_PWMH2{slash}PC20-Pad44)") (class "Default")
      (node (ref "IC1") (pin "44") (pinfunction "USART3_RTS/IISC_ISCK/EBI_DATA1/SCIF_GCLK1/PWM_PWMH2/PC20_44") (pintype "bidirectional"))
    )
    (net (code "59") (name "unconnected-(IC1D-USART3_RXD{slash}IISC_ISDI{slash}EBI_RAS{slash}EXTINT5{slash}PWM_PWML0{slash}PC18-Pad42)") (class "Default")
      (node (ref "IC1") (pin "42") (pinfunction "USART3_RXD/IISC_ISDI/EBI_RAS/EXTINT5/PWM_PWML0/PC18_42") (pintype "bidirectional"))
    )
    (net (code "60") (name "unconnected-(IC1D-USART3_TXD{slash}IISC_ISD0{slash}EBI_RAS{slash}SPI0_NPCS2{slash}PWM_PWMH0{slash}PC17-Pad41)") (class "Default")
      (node (ref "IC1") (pin "41") (pinfunction "USART3_TXD/IISC_ISD0/EBI_RAS/SPI0_NPCS2/PWM_PWMH0/PC17_41") (pintype "bidirectional"))
    )
    (net (code "61") (name "unconnected-(IC1E-MACB_RXD0{slash}PAD_EVT8{slash}EBI_SDCK{slash}USART1_CLK{slash}USART1_CTS{slash}PD13-Pad55)") (class "Default")
      (node (ref "IC1") (pin "55") (pinfunction "MACB_RXD0/PAD_EVT8/EBI_SDCK/USART1_CLK/USART1_CTS/PD13_55") (pintype "bidirectional"))
    )
    (net (code "62") (name "unconnected-(IC1E-MACB_RXD1{slash}PAD_EVT9{slash}EBI_ADDR10{slash}EXTINT7{slash}USART1_RTS{slash}PD14-Pad56)") (class "Default")
      (node (ref "IC1") (pin "56") (pinfunction "MACB_RXD1/PAD_EVT9/EBI_ADDR10/EXTINT7/USART1_RTS/PD14_56") (pintype "bidirectional"))
    )
    (net (code "63") (name "unconnected-(IC1E-MACB_TXD0{slash}PAD_EVT6{slash}EBI_ADDR8{slash}USBC_ID{slash}USART1_TXD{slash}PD11-Pad53)") (class "Default")
      (node (ref "IC1") (pin "53") (pinfunction "MACB_TXD0/PAD_EVT6/EBI_ADDR8/USBC_ID/USART1_TXD/PD11_53") (pintype "bidirectional"))
    )
    (net (code "64") (name "unconnected-(IC1E-MACB_TXD1{slash}PAD_EVT7{slash}EBI_ADDR9{slash}USBC_VBOF{slash}USART1_RXD{slash}PD12-Pad54)") (class "Default")
      (node (ref "IC1") (pin "54") (pinfunction "MACB_TXD1/PAD_EVT7/EBI_ADDR9/USBC_VBOF/USART1_RXD/PD12_54") (pintype "bidirectional"))
    )
    (net (code "65") (name "unconnected-(IC1E-MACB_TX_CLK{slash}TC0_CLK0{slash}USART0_CLK{slash}EXTINT6{slash}USART0_CTS{slash}PD29-Pad60)") (class "Default")
      (node (ref "IC1") (pin "60") (pinfunction "MACB_TX_CLK/TC0_CLK0/USART0_CLK/EXTINT6/USART0_CTS/PD29_60") (pintype "bidirectional"))
    )
    (net (code "66") (name "unconnected-(IC1E-MACB_TX_EN{slash}TC0_A1{slash}EBI_NWAIT{slash}EXTINT3{slash}USART0_RTS{slash}PD30-Pad61)") (class "Default")
      (node (ref "IC1") (pin "61") (pinfunction "MACB_TX_EN/TC0_A1/EBI_NWAIT/EXTINT3/USART0_RTS/PD30_61") (pintype "bidirectional"))
    )
    (net (code "67") (name "unconnected-(IC1E-QDEC1_QEPI{slash}EBI_ADDR17{slash}EXTINT0{slash}USART3_TXD{slash}PD21-Pad57)") (class "Default")
      (node (ref "IC1") (pin "57") (pinfunction "QDEC1_QEPI/EBI_ADDR17/EXTINT0/USART3_TXD/PD21_57") (pintype "bidirectional"))
    )
    (net (code "68") (name "unconnected-(IC1G-ADCVREFN-Pad15)") (class "Default")
      (node (ref "IC1") (pin "15") (pinfunction "ADCVREFN_15") (pintype "bidirectional"))
    )
    (net (code "69") (name "unconnected-(IC1G-ADCVREFP-Pad14)") (class "Default")
      (node (ref "IC1") (pin "14") (pinfunction "ADCVREFP_14") (pintype "bidirectional"))
    )
    (net (code "70") (name "unconnected-(IC3-VREF-Pad5)") (class "Default")
      (node (ref "IC3") (pin "5") (pinfunction "VREF_5") (pintype "bidirectional"))
    )
    (net (code "71") (name "unconnected-(IC4-VREF-Pad5)") (class "Default")
      (node (ref "IC4") (pin "5") (pinfunction "VREF_5") (pintype "bidirectional"))
    )
    (net (code "72") (name "unconnected-(IC7-CBUS0-Pad23)") (class "Default")
      (node (ref "IC7") (pin "23") (pinfunction "CBUS0_23") (pintype "bidirectional"))
    )
    (net (code "73") (name "unconnected-(IC7-CBUS1-Pad22)") (class "Default")
      (node (ref "IC7") (pin "22") (pinfunction "CBUS1_22") (pintype "bidirectional"))
    )
    (net (code "74") (name "unconnected-(IC7-CBUS2-Pad13)") (class "Default")
      (node (ref "IC7") (pin "13") (pinfunction "CBUS2_13") (pintype "bidirectional"))
    )
    (net (code "75") (name "unconnected-(IC7-CBUS3-Pad14)") (class "Default")
      (node (ref "IC7") (pin "14") (pinfunction "CBUS3_14") (pintype "bidirectional"))
    )
    (net (code "76") (name "unconnected-(IC7-CBUS4-Pad12)") (class "Default")
      (node (ref "IC7") (pin "12") (pinfunction "CBUS4_12") (pintype "bidirectional"))
    )
    (net (code "77") (name "unconnected-(IC7-OSCI-Pad27)") (class "Default")
      (node (ref "IC7") (pin "27") (pinfunction "OSCI_27") (pintype "input"))
    )
    (net (code "78") (name "unconnected-(IC7-OSCO-Pad28)") (class "Default")
      (node (ref "IC7") (pin "28") (pinfunction "OSCO_28") (pintype "output"))
    )
    (net (code "79") (name "unconnected-(IC7-~{CTS}-Pad11)") (class "Default")
      (node (ref "IC7") (pin "11") (pinfunction "~{CTS}_11") (pintype "input"))
    )
    (net (code "80") (name "unconnected-(IC7-~{DCD}-Pad10)") (class "Default")
      (node (ref "IC7") (pin "10") (pinfunction "~{DCD}_10") (pintype "input"))
    )
    (net (code "81") (name "unconnected-(IC7-~{DSR}-Pad9)") (class "Default")
      (node (ref "IC7") (pin "9") (pinfunction "~{DSR}_9") (pintype "input"))
    )
    (net (code "82") (name "unconnected-(IC7-~{DTR}-Pad2)") (class "Default")
      (node (ref "IC7") (pin "2") (pinfunction "~{DTR}_2") (pintype "output"))
    )
    (net (code "83") (name "unconnected-(IC7-~{RI}-Pad6)") (class "Default")
      (node (ref "IC7") (pin "6") (pinfunction "~{RI}_6") (pintype "input"))
    )
    (net (code "84") (name "unconnected-(IC7-~{RTS}-Pad3)") (class "Default")
      (node (ref "IC7") (pin "3") (pinfunction "~{RTS}_3") (pintype "output"))
    )
    (net (code "85") (name "unconnected-(SV1-Pad7)") (class "Default")
      (node (ref "SV1") (pin "7") (pinfunction "7_7") (pintype "passive"))
    )
    (net (code "86") (name "unconnected-(SV1-Pad8)") (class "Default")
      (node (ref "SV1") (pin "8") (pinfunction "8_8") (pintype "passive"))
    )
    (net (code "87") (name "unconnected-(X1-Pad1)") (class "Default")
      (node (ref "X1") (pin "1") (pinfunction "1_1") (pintype "passive"))
    )
    (net (code "88") (name "unconnected-(X1-Pad3)") (class "Default")
      (node (ref "X1") (pin "3") (pinfunction "3_3") (pintype "passive"))
    )
    (net (code "89") (name "unconnected-(X1-Pad4)") (class "Default")
      (node (ref "X1") (pin "4") (pinfunction "4_4") (pintype "passive"))
    )
    (net (code "90") (name "unconnected-(X1-Pad5)") (class "Default")
      (node (ref "X1") (pin "5") (pinfunction "5_5") (pintype "passive"))
    )
    (net (code "91") (name "unconnected-(X1-Pad6)") (class "Default")
      (node (ref "X1") (pin "6") (pinfunction "6_6") (pintype "passive"))
    )
    (net (code "92") (name "unconnected-(X1-Pad8)") (class "Default")
      (node (ref "X1") (pin "8") (pinfunction "8_8") (pintype "passive"))
    )
    (net (code "93") (name "unconnected-(X1-Pad9)") (class "Default")
      (node (ref "X1") (pin "9") (pinfunction "9_9") (pintype "passive"))
    )
    (net (code "94") (name "unconnected-(X2-Pad1)") (class "Default")
      (node (ref "X2") (pin "1") (pinfunction "1_1") (pintype "passive"))
    )
    (net (code "95") (name "unconnected-(X2-Pad3)") (class "Default")
      (node (ref "X2") (pin "3") (pinfunction "3_3") (pintype "passive"))
    )
    (net (code "96") (name "unconnected-(X2-Pad4)") (class "Default")
      (node (ref "X2") (pin "4") (pinfunction "4_4") (pintype "passive"))
    )
    (net (code "97") (name "unconnected-(X2-Pad5)") (class "Default")
      (node (ref "X2") (pin "5") (pinfunction "5_5") (pintype "passive"))
    )
    (net (code "98") (name "unconnected-(X2-Pad6)") (class "Default")
      (node (ref "X2") (pin "6") (pinfunction "6_6") (pintype "passive"))
    )
    (net (code "99") (name "unconnected-(X2-Pad8)") (class "Default")
      (node (ref "X2") (pin "8") (pinfunction "8_8") (pintype "passive"))
    )
    (net (code "100") (name "unconnected-(X2-Pad9)") (class "Default")
      (node (ref "X2") (pin "9") (pinfunction "9_9") (pintype "passive"))
    )
    (net (code "101") (name "~{RESET}") (class "Default")
      (node (ref "IC1") (pin "64") (pinfunction "~{RESET}_64") (pintype "bidirectional"))
      (node (ref "R1") (pin "1") (pinfunction "P$1_1") (pintype "passive"))
      (node (ref "S1") (pin "3") (pinfunction "P_3") (pintype "passive"))
      (node (ref "S1") (pin "4") (pinfunction "P1_4") (pintype "passive"))
      (node (ref "SV1") (pin "6") (pinfunction "6_6") (pintype "passive"))
    )
  )
)
